# v_reg.net
KiCad netlist of a schematic drawn in EAGLE
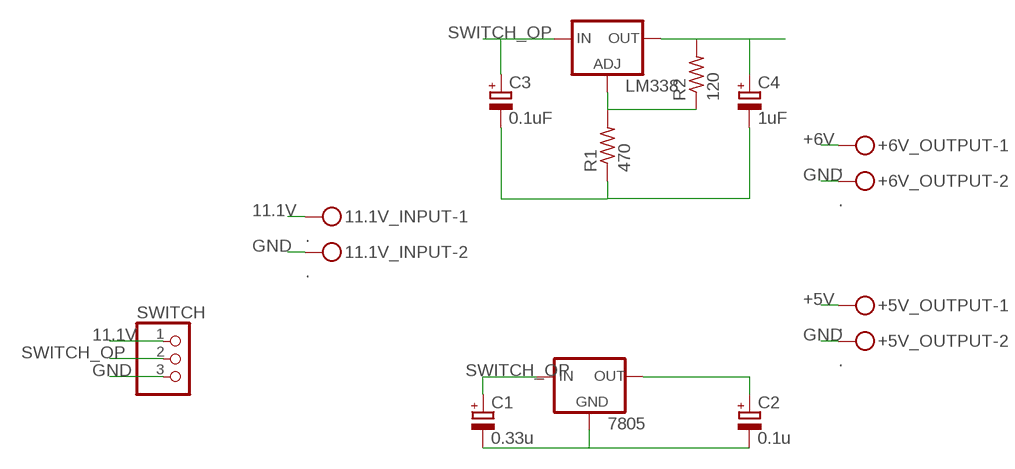
[diagram p0: schematic, sheet 1]

(export (version "E")
  (design (tool "Eeschema 10.0.6"))
  (components
    (comp (ref "+5V_OUTPUT")
      (value ".")
      (footprint "eagle-import:MKDSN1,5_2-5,08")
      (libsource (lib "eagle-import") (part "MKDSN1,5/2-5,08"))
    )
    (comp (ref "+6V_OUTPUT")
      (value ".")
      (footprint "eagle-import:MKDSN1,5_2-5,08")
      (libsource (lib "eagle-import") (part "MKDSN1,5/2-5,08"))
    )
    (comp (ref "11.1V_INPUT")
      (value ".")
      (footprint "eagle-import:MKDSN1,5_2-5,08")
      (libsource (lib "eagle-import") (part "MKDSN1,5/2-5,08"))
    )
    (comp (ref "7805")
      (value "78XXS")
      (footprint "eagle-import:78XXS")
      (libsource (lib "eagle-import") (part "78XXS"))
    )
    (comp (ref "C1")
      (value "0.33u")
      (footprint "eagle-import:E1,8-4")
      (libsource (lib "eagle-import") (part "CPOL-EUE1.8-4"))
    )
    (comp (ref "C2")
      (value "0.1u")
      (footprint "eagle-import:E1,8-4")
      (libsource (lib "eagle-import") (part "CPOL-EUE1.8-4"))
    )
    (comp (ref "C3")
      (value "0.1uF")
      (footprint "eagle-import:E1,8-4")
      (libsource (lib "eagle-import") (part "CPOL-EUE1.8-4"))
    )
    (comp (ref "C4")
      (value "1uF")
      (footprint "eagle-import:E1,8-4")
      (libsource (lib "eagle-import") (part "CPOL-EUE1.8-4"))
    )
    (comp (ref "LM338")
      (value "LM138-TS")
      (footprint "eagle-import:TO220S")
      (libsource (lib "eagle-import") (part "LM138-TS"))
    )
    (comp (ref "R1")
      (value "470")
      (footprint "eagle-import:0309_10")
      (libsource (lib "eagle-import") (part "R-US_0309/10"))
    )
    (comp (ref "R2")
      (value "120")
      (footprint "eagle-import:0309_10")
      (libsource (lib "eagle-import") (part "R-US_0309/10"))
    )
    (comp (ref "SWITCH")
      (value "PINHD-1X3")
      (footprint "eagle-import:1X03")
      (libsource (lib "eagle-import") (part "PINHD-1X3"))
    )
  )
  (nets
    (net (code "1") (name "/+5V") (class "Default")
      (node (ref "+5V_OUTPUT") (pin "1") (pinfunction "KL_1") (pintype "passive"))
      (node (ref "7805") (pin "OUT") (pinfunction "OUT_OUT") (pintype "passive"))
      (node (ref "C2") (pin "+") (pinfunction "+_+") (pintype "passive"))
    )
    (net (code "2") (name "/+6V") (class "Default")
      (node (ref "+6V_OUTPUT") (pin "1") (pinfunction "KL_1") (pintype "passive"))
      (node (ref "C4") (pin "+") (pinfunction "+_+") (pintype "passive"))
      (node (ref "LM338") (pin "2") (pinfunction "OUT_2") (pintype "passive"))
      (node (ref "R2") (pin "2") (pinfunction "2_2") (pintype "passive"))
    )
    (net (code "3") (name "/11.1V") (class "Default")
      (node (ref "11.1V_INPUT") (pin "1") (pinfunction "KL_1") (pintype "passive"))
      (node (ref "SWITCH") (pin "1") (pinfunction "1_1") (pintype "passive"))
    )
    (net (code "4") (name "/GND") (class "Default")
      (node (ref "+5V_OUTPUT") (pin "2") (pinfunction "KL_2") (pintype "passive"))
      (node (ref "+6V_OUTPUT") (pin "2") (pinfunction "KL_2") (pintype "passive"))
      (node (ref "11.1V_INPUT") (pin "2") (pinfunction "KL_2") (pintype "passive"))
      (node (ref "7805") (pin "GND") (pinfunction "GND_GND") (pintype "input"))
      (node (ref "C1") (pin "-") (pinfunction "-_-") (pintype "passive"))
      (node (ref "C2") (pin "-") (pinfunction "-_-") (pintype "passive"))
      (node (ref "C3") (pin "-") (pinfunction "-_-") (pintype "passive"))
      (node (ref "C4") (pin "-") (pinfunction "-_-") (pintype "passive"))
      (node (ref "R1") (pin "1") (pinfunction "1_1") (pintype "passive"))
      (node (ref "SWITCH") (pin "3") (pinfunction "3_3") (pintype "passive"))
    )
    (net (code "5") (name "/SWITCH_OP") (class "Default")
      (node (ref "7805") (pin "IN") (pinfunction "IN_IN") (pintype "input"))
      (node (ref "C1") (pin "+") (pinfunction "+_+") (pintype "passive"))
      (node (ref "C3") (pin "+") (pinfunction "+_+") (pintype "passive"))
      (node (ref "LM338") (pin "3") (pinfunction "IN_3") (pintype "input"))
      (node (ref "SWITCH") (pin "2") (pinfunction "2_2") (pintype "passive"))
    )
    (net (code "6") (name "Net-(LM338-ADJ)") (class "Default")
      (node (ref "LM338") (pin "1") (pinfunction "ADJ_1") (pintype "input"))
      (node (ref "R1") (pin "2") (pinfunction "2_2") (pintype "passive"))
      (node (ref "R2") (pin "1") (pinfunction "1_1") (pintype "passive"))
    )
  )
)
